# RFM22.net
KiCad netlist of a schematic drawn in Altium Designer
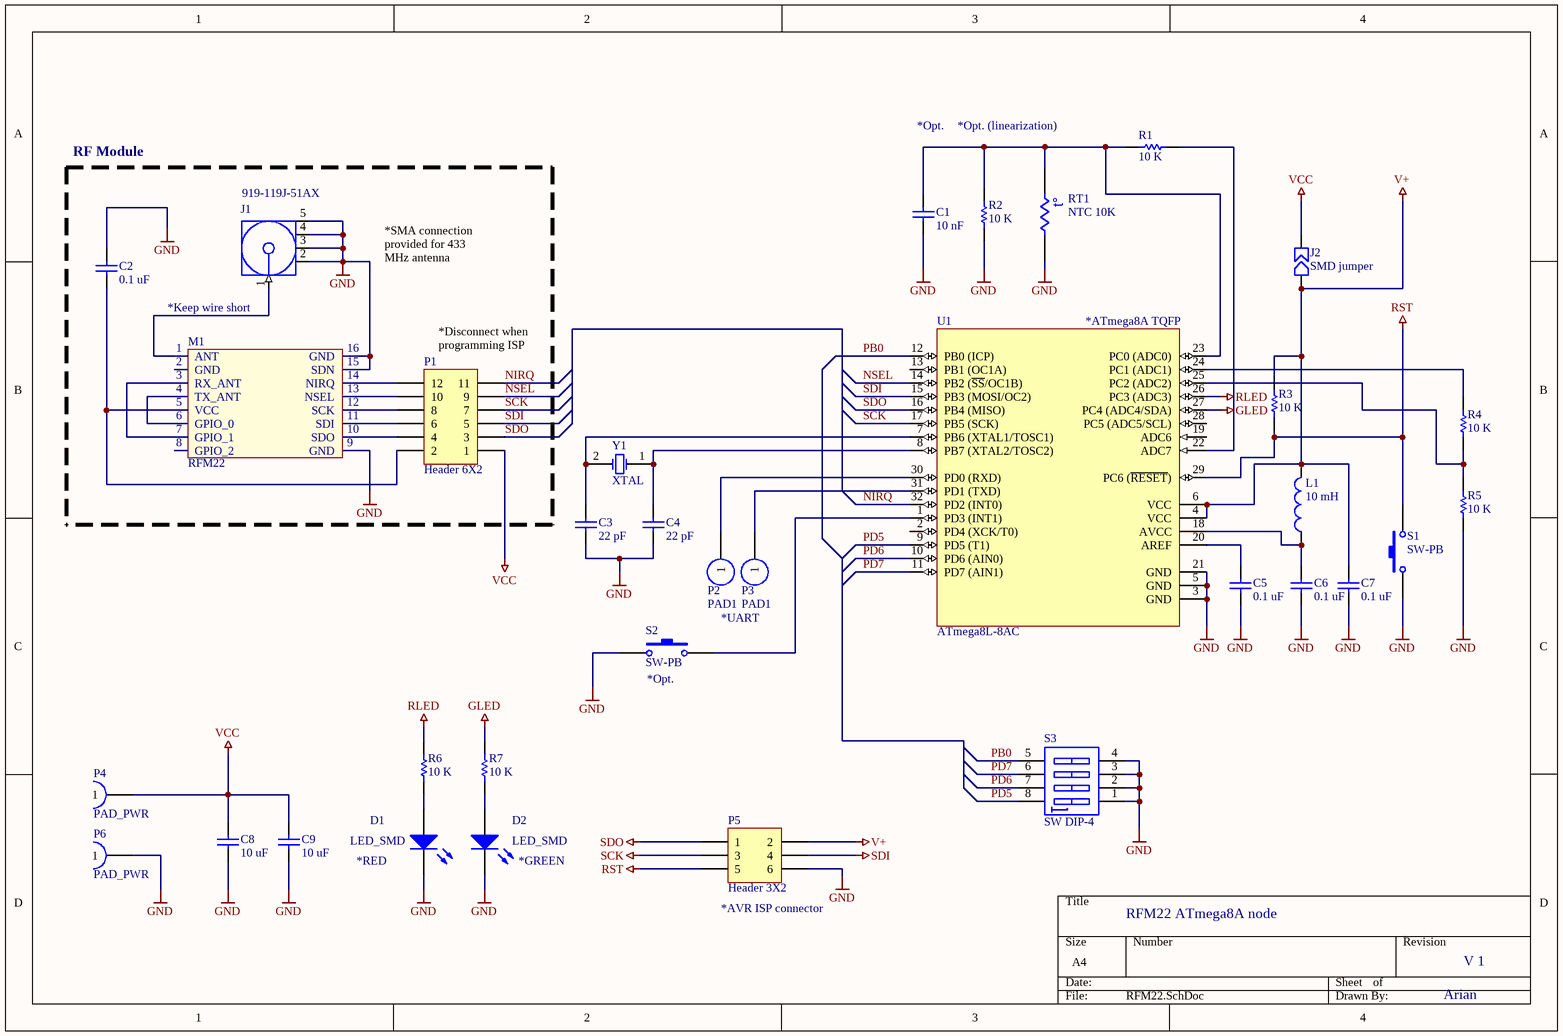
[diagram p0: RFM22.SchDoc]

(export (version "E")
  (design (tool "Eeschema 10.0.6"))
  (components
    (comp (ref "C1")
      (value "10 nF")
      (footprint "C0805")
      (description "Capacitor")
      (fields (field (name "PUBLISHER") "Altium Limited"))
      (libsource (lib "RFM22") (part "Cap"))
    )
    (comp (ref "C2")
      (value "0.1 uF")
      (footprint "C0805")
      (description "Capacitor")
      (fields (field (name "PUBLISHER") "Altium Limited"))
      (libsource (lib "RFM22") (part "Cap"))
    )
    (comp (ref "C3")
      (value "22 pF")
      (footprint "C0805")
      (description "Capacitor")
      (fields (field (name "PUBLISHER") "Altium Limited"))
      (libsource (lib "RFM22") (part "Cap"))
    )
    (comp (ref "C4")
      (value "22 pF")
      (footprint "C0805")
      (description "Capacitor")
      (fields (field (name "PUBLISHER") "Altium Limited"))
      (libsource (lib "RFM22") (part "Cap"))
    )
    (comp (ref "C5")
      (value "0.1 uF")
      (footprint "C0805")
      (description "Capacitor")
      (fields (field (name "PUBLISHER") "Altium Limited"))
      (libsource (lib "RFM22") (part "Cap"))
    )
    (comp (ref "C6")
      (value "0.1 uF")
      (footprint "C0805")
      (description "Capacitor")
      (fields (field (name "PUBLISHER") "Altium Limited"))
      (libsource (lib "RFM22") (part "Cap"))
    )
    (comp (ref "C7")
      (value "0.1 uF")
      (footprint "C0805")
      (description "Capacitor")
      (fields (field (name "PUBLISHER") "Altium Limited"))
      (libsource (lib "RFM22") (part "Cap"))
    )
    (comp (ref "C8")
      (value "10 uF")
      (footprint "C0805")
      (description "Capacitor")
      (fields (field (name "PUBLISHER") "Altium Limited"))
      (libsource (lib "RFM22") (part "Cap"))
    )
    (comp (ref "C9")
      (value "10 uF")
      (footprint "C0805")
      (description "Capacitor")
      (fields (field (name "PUBLISHER") "Altium Limited"))
      (libsource (lib "RFM22") (part "Cap"))
    )
    (comp (ref "D1")
      (value "LED_SMD")
      (footprint "LED-0805")
      (description "Typical SMD LED")
      (fields (field (name "PUBLISHER") "Altium Limited"))
      (libsource (lib "RFM22") (part "LED_SMD"))
    )
    (comp (ref "D2")
      (value "LED_SMD")
      (footprint "LED-0805")
      (description "Typical SMD LED")
      (fields (field (name "PUBLISHER") "Altium Limited"))
      (libsource (lib "RFM22") (part "LED_SMD"))
    )
    (comp (ref "J1")
      (value "919-119J-51AX")
      (footprint "919-119J")
      (fields (field (name "PUBLISHER") "Altium Limited"))
      (libsource (lib "Amphenol RF Coaxial MCX") (part "919-119J-51AX"))
    )
    (comp (ref "J2")
      (value "SMD jumper")
      (footprint "SMD jmp 2")
      (libsource (lib "RFM22") (part "SMD jumper"))
    )
    (comp (ref "L1")
      (value "10 mH")
      (footprint "1812")
      (description "Inductor")
      (fields (field (name "PUBLISHER") "Altium Limited"))
      (libsource (lib "RFM22") (part "Inductor"))
    )
    (comp (ref "M1") (value "RFM22") (footprint "RFM22_S2") (libsource (lib "RFM22") (part "RFM22")))
    (comp (ref "P1")
      (value "Header 6X2")
      (footprint "HDR2X6")
      (description "Header, 6-Pin, Dual row")
      (fields (field (name "PUBLISHER") "Altium Limited"))
      (libsource (lib "Miscellaneous Connectors") (part "Header 6X2"))
    )
    (comp (ref "P2")
      (value "PAD1")
      (footprint "PAD1")
      (description "PAD connection")
      (fields (field (name "PUBLISHER") "Altium Limited"))
      (libsource (lib "RFM22") (part "PAD1"))
    )
    (comp (ref "P3")
      (value "PAD1")
      (footprint "PAD1")
      (description "PAD connection")
      (fields (field (name "PUBLISHER") "Altium Limited"))
      (libsource (lib "RFM22") (part "PAD1"))
    )
    (comp (ref "P4")
      (value "PAD_PWR")
      (footprint "PAD_PWR")
      (description "PAD connection")
      (fields (field (name "PUBLISHER") "Altium Limited"))
      (libsource (lib "RFM22") (part "PAD_PWR"))
    )
    (comp (ref "P5")
      (value "Header 3X2")
      (footprint "HDR2X3")
      (description "Header, 3-Pin, Dual row")
      (fields (field (name "PUBLISHER") "Altium Limited"))
      (libsource (lib "Miscellaneous Connectors") (part "Header 3X2"))
    )
    (comp (ref "P6")
      (value "PAD_PWR")
      (footprint "PAD_PWR")
      (description "PAD connection")
      (fields (field (name "PUBLISHER") "Altium Limited"))
      (libsource (lib "RFM22") (part "PAD_PWR"))
    )
    (comp (ref "R1")
      (value "10 K")
      (footprint "R0805")
      (description "Resistor")
      (fields (field (name "PUBLISHER") "Altium Limited"))
      (libsource (lib "RFM22") (part "Res1"))
    )
    (comp (ref "R2")
      (value "10 K")
      (footprint "R0805")
      (description "Resistor")
      (fields (field (name "PUBLISHER") "Altium Limited"))
      (libsource (lib "RFM22") (part "Res1"))
    )
    (comp (ref "R3")
      (value "10 K")
      (footprint "R0805")
      (description "Resistor")
      (fields (field (name "PUBLISHER") "Altium Limited"))
      (libsource (lib "RFM22") (part "Res1"))
    )
    (comp (ref "R4")
      (value "10 K")
      (footprint "R0805")
      (description "Resistor")
      (fields (field (name "PUBLISHER") "Altium Limited"))
      (libsource (lib "RFM22") (part "Res1"))
    )
    (comp (ref "R5")
      (value "10 K")
      (footprint "R0805")
      (description "Resistor")
      (fields (field (name "PUBLISHER") "Altium Limited"))
      (libsource (lib "RFM22") (part "Res1"))
    )
    (comp (ref "R6")
      (value "10 K")
      (footprint "R0805")
      (description "Resistor")
      (fields (field (name "PUBLISHER") "Altium Limited"))
      (libsource (lib "RFM22") (part "Res1"))
    )
    (comp (ref "R7")
      (value "10 K")
      (footprint "R0805")
      (description "Resistor")
      (fields (field (name "PUBLISHER") "Altium Limited"))
      (libsource (lib "RFM22") (part "Res1"))
    )
    (comp (ref "RT1")
      (value "NTC 10K")
      (footprint "R1206")
      (description "Thermistor")
      (fields (field (name "PUBLISHER") "Altium Limited"))
      (libsource (lib "RFM22") (part "Res Thermal"))
    )
    (comp (ref "S1")
      (value "SW-PB")
      (footprint "SW_ts017a")
      (description "Switch")
      (fields (field (name "PUBLISHER") "Altium Limited"))
      (libsource (lib "RFM22") (part "SW-PB"))
    )
    (comp (ref "S2")
      (value "SW-PB")
      (footprint "SW_ts017a")
      (description "Switch")
      (fields (field (name "PUBLISHER") "Altium Limited"))
      (libsource (lib "RFM22") (part "SW-PB"))
    )
    (comp (ref "S3")
      (value "SW DIP-4")
      (footprint "DIP-8")
      (description "DIP Switch, 4 Position, SPST")
      (fields (field (name "PUBLISHER") "Altium Limited"))
      (libsource (lib "RFM22") (part "SW DIP-4"))
    )
    (comp (ref "U1")
      (value "ATmega8L-8AC")
      (footprint "32A_N")
      (description "8-Bit AVR Microcontroller with 8K Bytes of In-System Programmable Flash Memory")
      (fields (field (name "PUBLISHER") "Altium Limited"))
      (libsource (lib "Atmel Microcontroller 8-Bit AVR") (part "ATmega8L-8AC"))
    )
    (comp (ref "Y1")
      (value "XTAL")
      (footprint "X32768_normal")
      (description "Crystal Oscillator")
      (fields (field (name "PUBLISHER") "Altium Limited"))
      (libsource (lib "RFM22") (part "XTAL"))
    )
  )
  (nets
    (net (code "1") (name "/NIRQ") (class "Default")
      (node (ref "P1") (pin "11") (pinfunction "11_11") (pintype "passive"))
      (node (ref "U1") (pin "32") (pinfunction "PD2_(INT0)_32") (pintype "bidirectional"))
    )
    (net (code "2") (name "/NSEL") (class "Default")
      (node (ref "P1") (pin "9") (pinfunction "9_9") (pintype "passive"))
      (node (ref "U1") (pin "14") (pinfunction "PB2_(~{SS}/OC1B)_14") (pintype "bidirectional"))
    )
    (net (code "3") (name "/PB0") (class "Default")
      (node (ref "S3") (pin "5") (pinfunction "B4_5") (pintype "passive"))
      (node (ref "U1") (pin "12") (pinfunction "PB0_(ICP)_12") (pintype "bidirectional"))
    )
    (net (code "4") (name "/PD5") (class "Default")
      (node (ref "S3") (pin "8") (pinfunction "B1_8") (pintype "passive"))
      (node (ref "U1") (pin "9") (pinfunction "PD5_(T1)_9") (pintype "bidirectional"))
    )
    (net (code "5") (name "/PD6") (class "Default")
      (node (ref "S3") (pin "7") (pinfunction "B2_7") (pintype "passive"))
      (node (ref "U1") (pin "10") (pinfunction "PD6_(AIN0)_10") (pintype "bidirectional"))
    )
    (net (code "6") (name "/PD7") (class "Default")
      (node (ref "S3") (pin "6") (pinfunction "B3_6") (pintype "passive"))
      (node (ref "U1") (pin "11") (pinfunction "PD7_(AIN1)_11") (pintype "bidirectional"))
    )
    (net (code "7") (name "GLED") (class "Default")
      (node (ref "R7") (pin "1") (pinfunction "1_1") (pintype "passive"))
      (node (ref "U1") (pin "27") (pinfunction "PC4_(ADC4/SDA)_27") (pintype "bidirectional"))
    )
    (net (code "8") (name "GND") (class "Default")
      (node (ref "C1") (pin "1") (pinfunction "1_1") (pintype "passive"))
      (node (ref "C2") (pin "2") (pinfunction "2_2") (pintype "passive"))
      (node (ref "C3") (pin "1") (pinfunction "1_1") (pintype "passive"))
      (node (ref "C4") (pin "1") (pinfunction "1_1") (pintype "passive"))
      (node (ref "C5") (pin "1") (pinfunction "1_1") (pintype "passive"))
      (node (ref "C6") (pin "1") (pinfunction "1_1") (pintype "passive"))
      (node (ref "C7") (pin "1") (pinfunction "1_1") (pintype "passive"))
      (node (ref "C8") (pin "1") (pinfunction "1_1") (pintype "passive"))
      (node (ref "C9") (pin "1") (pinfunction "1_1") (pintype "passive"))
      (node (ref "D1") (pin "2") (pinfunction "K_2") (pintype "passive"))
      (node (ref "D2") (pin "2") (pinfunction "K_2") (pintype "passive"))
      (node (ref "J1") (pin "2") (pinfunction "GND_2") (pintype "power_in"))
      (node (ref "J1") (pin "3") (pinfunction "GND_3") (pintype "power_in"))
      (node (ref "J1") (pin "4") (pinfunction "GND_4") (pintype "power_in"))
      (node (ref "J1") (pin "5") (pinfunction "GND_5") (pintype "power_in"))
      (node (ref "M1") (pin "15") (pinfunction "SDN_15") (pintype "passive"))
      (node (ref "M1") (pin "16") (pinfunction "GND_16") (pintype "power_in"))
      (node (ref "M1") (pin "9") (pinfunction "GND_9") (pintype "passive"))
      (node (ref "P5") (pin "6") (pinfunction "6_6") (pintype "passive"))
      (node (ref "P6") (pin "1") (pinfunction "1_1") (pintype "passive"))
      (node (ref "R2") (pin "2") (pinfunction "2_2") (pintype "passive"))
      (node (ref "R5") (pin "1") (pinfunction "1_1") (pintype "passive"))
      (node (ref "RT1") (pin "2") (pinfunction "2_2") (pintype "passive"))
      (node (ref "S1") (pin "1") (pinfunction "1_1") (pintype "passive"))
      (node (ref "S2") (pin "1") (pinfunction "1_1") (pintype "passive"))
      (node (ref "S3") (pin "1") (pinfunction "A1_1") (pintype "passive"))
      (node (ref "S3") (pin "2") (pinfunction "A2_2") (pintype "passive"))
      (node (ref "S3") (pin "3") (pinfunction "A3_3") (pintype "passive"))
      (node (ref "S3") (pin "4") (pinfunction "A4_4") (pintype "passive"))
      (node (ref "U1") (pin "21") (pinfunction "GND_21") (pintype "power_in"))
      (node (ref "U1") (pin "3") (pinfunction "GND_3") (pintype "power_in"))
      (node (ref "U1") (pin "5") (pinfunction "GND_5") (pintype "power_in"))
    )
    (net (code "9") (name "Net-(D1-A)") (class "Default")
      (node (ref "D1") (pin "1") (pinfunction "A_1") (pintype "passive"))
      (node (ref "R6") (pin "2") (pinfunction "2_2") (pintype "passive"))
    )
    (net (code "10") (name "Net-(D2-A)") (class "Default")
      (node (ref "D2") (pin "1") (pinfunction "A_1") (pintype "passive"))
      (node (ref "R7") (pin "2") (pinfunction "2_2") (pintype "passive"))
    )
    (net (code "11") (name "Net-(J1-Signal)") (class "Default")
      (node (ref "J1") (pin "1") (pinfunction "Signal_1") (pintype "input"))
      (node (ref "M1") (pin "1") (pinfunction "ANT_1") (pintype "passive"))
    )
    (net (code "12") (name "Net-(M1-GPIO_0)") (class "Default")
      (node (ref "M1") (pin "4") (pinfunction "TX_ANT_4") (pintype "passive"))
      (node (ref "M1") (pin "6") (pinfunction "GPIO_0_6") (pintype "passive"))
    )
    (net (code "13") (name "Net-(M1-GPIO_1)") (class "Default")
      (node (ref "M1") (pin "3") (pinfunction "RX_ANT_3") (pintype "passive"))
      (node (ref "M1") (pin "7") (pinfunction "GPIO_1_7") (pintype "passive"))
    )
    (net (code "14") (name "Net-(M1-NIRQ)") (class "Default")
      (node (ref "M1") (pin "14") (pinfunction "NIRQ_14") (pintype "passive"))
      (node (ref "P1") (pin "12") (pinfunction "12_12") (pintype "passive"))
    )
    (net (code "15") (name "Net-(M1-NSEL)") (class "Default")
      (node (ref "M1") (pin "13") (pinfunction "NSEL_13") (pintype "passive"))
      (node (ref "P1") (pin "10") (pinfunction "10_10") (pintype "passive"))
    )
    (net (code "16") (name "Net-(M1-SCK)") (class "Default")
      (node (ref "M1") (pin "12") (pinfunction "SCK_12") (pintype "passive"))
      (node (ref "P1") (pin "8") (pinfunction "8_8") (pintype "passive"))
    )
    (net (code "17") (name "Net-(M1-SDI)") (class "Default")
      (node (ref "M1") (pin "11") (pinfunction "SDI_11") (pintype "passive"))
      (node (ref "P1") (pin "6") (pinfunction "6_6") (pintype "passive"))
    )
    (net (code "18") (name "Net-(M1-SDO)") (class "Default")
      (node (ref "M1") (pin "10") (pinfunction "SDO_10") (pintype "passive"))
      (node (ref "P1") (pin "4") (pinfunction "4_4") (pintype "passive"))
    )
    (net (code "19") (name "Net-(M1-VCC)") (class "Default")
      (node (ref "C2") (pin "1") (pinfunction "1_1") (pintype "passive"))
      (node (ref "M1") (pin "5") (pinfunction "VCC_5") (pintype "passive"))
      (node (ref "P1") (pin "2") (pinfunction "2_2") (pintype "passive"))
    )
    (net (code "20") (name "Net-(U1-ADC7)") (class "Default")
      (node (ref "R1") (pin "2") (pinfunction "2_2") (pintype "passive"))
      (node (ref "U1") (pin "22") (pinfunction "ADC7_22") (pintype "input"))
    )
    (net (code "21") (name "Net-(U1-AREF)") (class "Default")
      (node (ref "C5") (pin "2") (pinfunction "2_2") (pintype "passive"))
      (node (ref "U1") (pin "20") (pinfunction "AREF_20") (pintype "passive"))
    )
    (net (code "22") (name "Net-(U1-AVCC)") (class "Default")
      (node (ref "C6") (pin "2") (pinfunction "2_2") (pintype "passive"))
      (node (ref "L1") (pin "1") (pinfunction "1_1") (pintype "passive"))
      (node (ref "U1") (pin "18") (pinfunction "AVCC_18") (pintype "power_in"))
    )
    (net (code "23") (name "Net-(U1-PB6_(XTAL1{slash}TOSC1))") (class "Default")
      (node (ref "C3") (pin "2") (pinfunction "2_2") (pintype "passive"))
      (node (ref "U1") (pin "7") (pinfunction "PB6_(XTAL1/TOSC1)_7") (pintype "bidirectional"))
      (node (ref "Y1") (pin "2") (pinfunction "OSC2_2") (pintype "passive"))
    )
    (net (code "24") (name "Net-(U1-PB7_(XTAL2{slash}TOSC2))") (class "Default")
      (node (ref "C4") (pin "2") (pinfunction "2_2") (pintype "passive"))
      (node (ref "U1") (pin "8") (pinfunction "PB7_(XTAL2/TOSC2)_8") (pintype "bidirectional"))
      (node (ref "Y1") (pin "1") (pinfunction "OSC1_1") (pintype "passive"))
    )
    (net (code "25") (name "Net-(U1-PC0_(ADC0))") (class "Default")
      (node (ref "C1") (pin "2") (pinfunction "2_2") (pintype "passive"))
      (node (ref "R1") (pin "1") (pinfunction "1_1") (pintype "passive"))
      (node (ref "R2") (pin "1") (pinfunction "1_1") (pintype "passive"))
      (node (ref "RT1") (pin "1") (pinfunction "1_1") (pintype "passive"))
      (node (ref "U1") (pin "23") (pinfunction "PC0_(ADC0)_23") (pintype "bidirectional"))
    )
    (net (code "26") (name "Net-(U1-PC1_(ADC1))") (class "Default")
      (node (ref "R4") (pin "2") (pinfunction "2_2") (pintype "passive"))
      (node (ref "U1") (pin "24") (pinfunction "PC1_(ADC1)_24") (pintype "bidirectional"))
    )
    (net (code "27") (name "Net-(U1-PC2_(ADC2))") (class "Default")
      (node (ref "R4") (pin "1") (pinfunction "1_1") (pintype "passive"))
      (node (ref "R5") (pin "2") (pinfunction "2_2") (pintype "passive"))
      (node (ref "U1") (pin "25") (pinfunction "PC2_(ADC2)_25") (pintype "bidirectional"))
    )
    (net (code "28") (name "Net-(U1-PD0_(RXD))") (class "Default")
      (node (ref "P2") (pin "1") (pinfunction "1_1") (pintype "passive"))
      (node (ref "U1") (pin "30") (pinfunction "PD0_(RXD)_30") (pintype "bidirectional"))
    )
    (net (code "29") (name "Net-(U1-PD1_(TXD))") (class "Default")
      (node (ref "P3") (pin "1") (pinfunction "1_1") (pintype "passive"))
      (node (ref "U1") (pin "31") (pinfunction "PD1_(TXD)_31") (pintype "bidirectional"))
    )
    (net (code "30") (name "Net-(U1-PD3_(INT1))") (class "Default")
      (node (ref "S2") (pin "2") (pinfunction "2_2") (pintype "passive"))
      (node (ref "U1") (pin "1") (pinfunction "PD3_(INT1)_1") (pintype "bidirectional"))
    )
    (net (code "31") (name "RLED") (class "Default")
      (node (ref "R6") (pin "1") (pinfunction "1_1") (pintype "passive"))
      (node (ref "U1") (pin "26") (pinfunction "PC3_(ADC3)_26") (pintype "bidirectional"))
    )
    (net (code "32") (name "RST") (class "Default")
      (node (ref "P5") (pin "5") (pinfunction "5_5") (pintype "passive"))
      (node (ref "R3") (pin "2") (pinfunction "2_2") (pintype "passive"))
      (node (ref "S1") (pin "2") (pinfunction "2_2") (pintype "passive"))
      (node (ref "U1") (pin "29") (pinfunction "PC6_(~{RESET})_29") (pintype "bidirectional"))
    )
    (net (code "33") (name "SCK") (class "Default")
      (node (ref "P1") (pin "7") (pinfunction "7_7") (pintype "passive"))
      (node (ref "P5") (pin "3") (pinfunction "3_3") (pintype "passive"))
      (node (ref "U1") (pin "17") (pinfunction "PB5_(SCK)_17") (pintype "bidirectional"))
    )
    (net (code "34") (name "SDI") (class "Default")
      (node (ref "P1") (pin "5") (pinfunction "5_5") (pintype "passive"))
      (node (ref "P5") (pin "4") (pinfunction "4_4") (pintype "passive"))
      (node (ref "U1") (pin "15") (pinfunction "PB3_(MOSI/OC2)_15") (pintype "bidirectional"))
    )
    (net (code "35") (name "SDO") (class "Default")
      (node (ref "P1") (pin "3") (pinfunction "3_3") (pintype "passive"))
      (node (ref "P5") (pin "1") (pinfunction "1_1") (pintype "passive"))
      (node (ref "U1") (pin "16") (pinfunction "PB4_(MISO)_16") (pintype "bidirectional"))
    )
    (net (code "36") (name "V+") (class "Default")
      (node (ref "C7") (pin "2") (pinfunction "2_2") (pintype "passive"))
      (node (ref "J2") (pin "1") (pinfunction "1_1") (pintype "passive"))
      (node (ref "L1") (pin "2") (pinfunction "2_2") (pintype "passive"))
      (node (ref "P5") (pin "2") (pinfunction "2_2") (pintype "passive"))
      (node (ref "R3") (pin "1") (pinfunction "1_1") (pintype "passive"))
      (node (ref "U1") (pin "4") (pinfunction "VCC_4") (pintype "power_in"))
      (node (ref "U1") (pin "6") (pinfunction "VCC_6") (pintype "power_in"))
    )
    (net (code "37") (name "VCC") (class "Default")
      (node (ref "C8") (pin "2") (pinfunction "2_2") (pintype "passive"))
      (node (ref "C9") (pin "2") (pinfunction "2_2") (pintype "passive"))
      (node (ref "J2") (pin "2") (pinfunction "2_2") (pintype "passive"))
      (node (ref "P1") (pin "1") (pinfunction "1_1") (pintype "passive"))
      (node (ref "P4") (pin "1") (pinfunction "1_1") (pintype "passive"))
    )
    (net (code "38") (name "unconnected-(M1-GND-Pad2)") (class "Default")
      (node (ref "M1") (pin "2") (pinfunction "GND_2") (pintype "passive"))
    )
    (net (code "39") (name "unconnected-(M1-GPIO_2-Pad8)") (class "Default")
      (node (ref "M1") (pin "8") (pinfunction "GPIO_2_8") (pintype "passive"))
    )
    (net (code "40") (name "unconnected-(U1-ADC6-Pad19)") (class "Default")
      (node (ref "U1") (pin "19") (pinfunction "ADC6_19") (pintype "input"))
    )
    (net (code "41") (name "unconnected-(U1-PB1_(OC1A)-Pad13)") (class "Default")
      (node (ref "U1") (pin "13") (pinfunction "PB1_(OC1A)_13") (pintype "bidirectional"))
    )
    (net (code "42") (name "unconnected-(U1-PC5_(ADC5{slash}SCL)-Pad28)") (class "Default")
      (node (ref "U1") (pin "28") (pinfunction "PC5_(ADC5/SCL)_28") (pintype "bidirectional"))
    )
    (net (code "43") (name "unconnected-(U1-PD4_(XCK{slash}T0)-Pad2)") (class "Default")
      (node (ref "U1") (pin "2") (pinfunction "PD4_(XCK/T0)_2") (pintype "bidirectional"))
    )
  )
)
